# 5_sd_card.net
KiCad netlist of a schematic drawn in Altium Designer
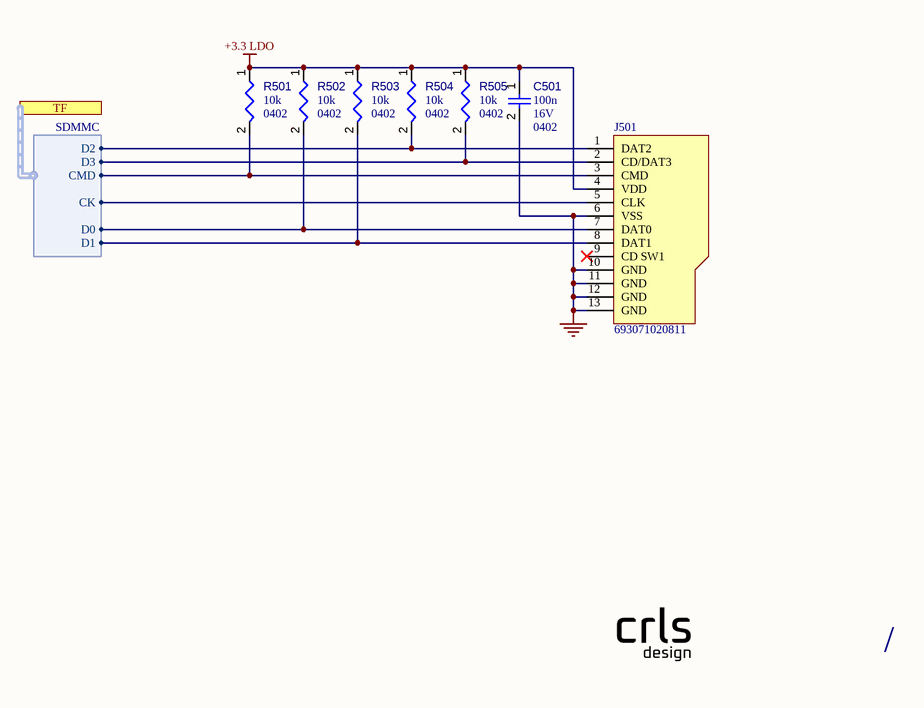
[diagram p0: 5 sd card.SchDoc]

(export (version "E")
  (design (tool "Eeschema 10.0.6"))
  (components
    (comp (ref "C501")
      (value "100n")
      (footprint "CAPC0402(1005)60_L")
      (description "Capacitor")
      (fields
        (field (name "CASE/PACKAGE") "0402")
        (field (name "VOLTAGE RATING") "16V")
        (field (name "Comment") "Capacitors,0402,100n,16V")
      )
      (libsource (lib "UBC Uncrewed Aircraft Systems") (part "CAP-NP-2"))
    )
    (comp (ref "J501")
      (value "693071020811")
      (footprint "693071020811")
      (description "693071020811 Micro Sd Card, Push-Push, 8Pos, Smt Rohs Compliant: Yes")
      (libsource (lib "Altium Content Vault") (part "693071020811"))
    )
    (comp (ref "R501")
      (value "10k")
      (footprint "RESC0402(1005)_L")
      (description "Resistor")
      (fields
        (field (name "CASE/PACKAGE") "0402")
        (field (name "TOLERANCE") "1%")
        (field (name "Comment") "Resistors,0402,1%,10k")
      )
      (libsource (lib "UBC Uncrewed Aircraft Systems") (part "RES-2"))
    )
    (comp (ref "R502")
      (value "10k")
      (footprint "RESC0402(1005)_L")
      (description "Resistor")
      (fields
        (field (name "CASE/PACKAGE") "0402")
        (field (name "TOLERANCE") "1%")
        (field (name "Comment") "Resistors,0402,1%,10k")
      )
      (libsource (lib "UBC Uncrewed Aircraft Systems") (part "RES-2"))
    )
    (comp (ref "R503")
      (value "10k")
      (footprint "RESC0402(1005)_L")
      (description "Resistor")
      (fields
        (field (name "CASE/PACKAGE") "0402")
        (field (name "TOLERANCE") "1%")
        (field (name "Comment") "Resistors,0402,1%,10k")
      )
      (libsource (lib "UBC Uncrewed Aircraft Systems") (part "RES-2"))
    )
    (comp (ref "R504")
      (value "10k")
      (footprint "RESC0402(1005)_L")
      (description "Resistor")
      (fields
        (field (name "CASE/PACKAGE") "0402")
        (field (name "TOLERANCE") "1%")
        (field (name "Comment") "Resistors,0402,1%,10k")
      )
      (libsource (lib "UBC Uncrewed Aircraft Systems") (part "RES-2"))
    )
    (comp (ref "R505")
      (value "10k")
      (footprint "RESC0402(1005)_L")
      (description "Resistor")
      (fields
        (field (name "CASE/PACKAGE") "0402")
        (field (name "TOLERANCE") "1%")
        (field (name "Comment") "Resistors,0402,1%,10k")
      )
      (libsource (lib "UBC Uncrewed Aircraft Systems") (part "RES-2"))
    )
  )
  (nets
    (net (code "2") (name "+3.3 LDO") (class "Default")
      (node (ref "C501") (pin "1") (pinfunction "1_1") (pintype "passive"))
      (node (ref "J501") (pin "4") (pinfunction "VDD_4") (pintype "passive"))
      (node (ref "R501") (pin "1") (pinfunction "1_1") (pintype "passive"))
      (node (ref "R502") (pin "1") (pinfunction "1_1") (pintype "passive"))
      (node (ref "R503") (pin "1") (pinfunction "1_1") (pintype "passive"))
      (node (ref "R504") (pin "1") (pinfunction "1_1") (pintype "passive"))
      (node (ref "R505") (pin "1") (pinfunction "1_1") (pintype "passive"))
    )
    (net (code "3") (name "/CK") (class "Default")
      (node (ref "J501") (pin "5") (pinfunction "CLK_5") (pintype "passive"))
    )
    (net (code "4") (name "/CMD") (class "Default")
      (node (ref "J501") (pin "3") (pinfunction "CMD_3") (pintype "passive"))
      (node (ref "R501") (pin "2") (pinfunction "2_2") (pintype "passive"))
    )
    (net (code "5") (name "/D0") (class "Default")
      (node (ref "J501") (pin "7") (pinfunction "DAT0_7") (pintype "passive"))
      (node (ref "R502") (pin "2") (pinfunction "2_2") (pintype "passive"))
    )
    (net (code "6") (name "/D1") (class "Default")
      (node (ref "J501") (pin "8") (pinfunction "DAT1_8") (pintype "passive"))
      (node (ref "R503") (pin "2") (pinfunction "2_2") (pintype "passive"))
    )
    (net (code "7") (name "/D2") (class "Default")
      (node (ref "J501") (pin "1") (pinfunction "DAT2_1") (pintype "passive"))
      (node (ref "R504") (pin "2") (pinfunction "2_2") (pintype "passive"))
    )
    (net (code "8") (name "/D3") (class "Default")
      (node (ref "J501") (pin "2") (pinfunction "CD/DAT3_2") (pintype "passive"))
      (node (ref "R505") (pin "2") (pinfunction "2_2") (pintype "passive"))
    )
    (net (code "10") (name "GND") (class "Default")
      (node (ref "C501") (pin "2") (pinfunction "2_2") (pintype "passive"))
      (node (ref "J501") (pin "10") (pinfunction "GND_10") (pintype "passive"))
      (node (ref "J501") (pin "11") (pinfunction "GND_11") (pintype "passive"))
      (node (ref "J501") (pin "12") (pinfunction "GND_12") (pintype "passive"))
      (node (ref "J501") (pin "13") (pinfunction "GND_13") (pintype "passive"))
      (node (ref "J501") (pin "6") (pinfunction "VSS_6") (pintype "passive"))
    )
    (net (code "11") (name "unconnected-(J501-CD_SW1-Pad9)") (class "Default")
      (node (ref "J501") (pin "9") (pinfunction "CD_SW1_9") (pintype "passive+no_connect"))
    )
  )
)
